# Adafruit_FTDI_Friend_Rev_A.net
KiCad netlist of a schematic drawn in EAGLE
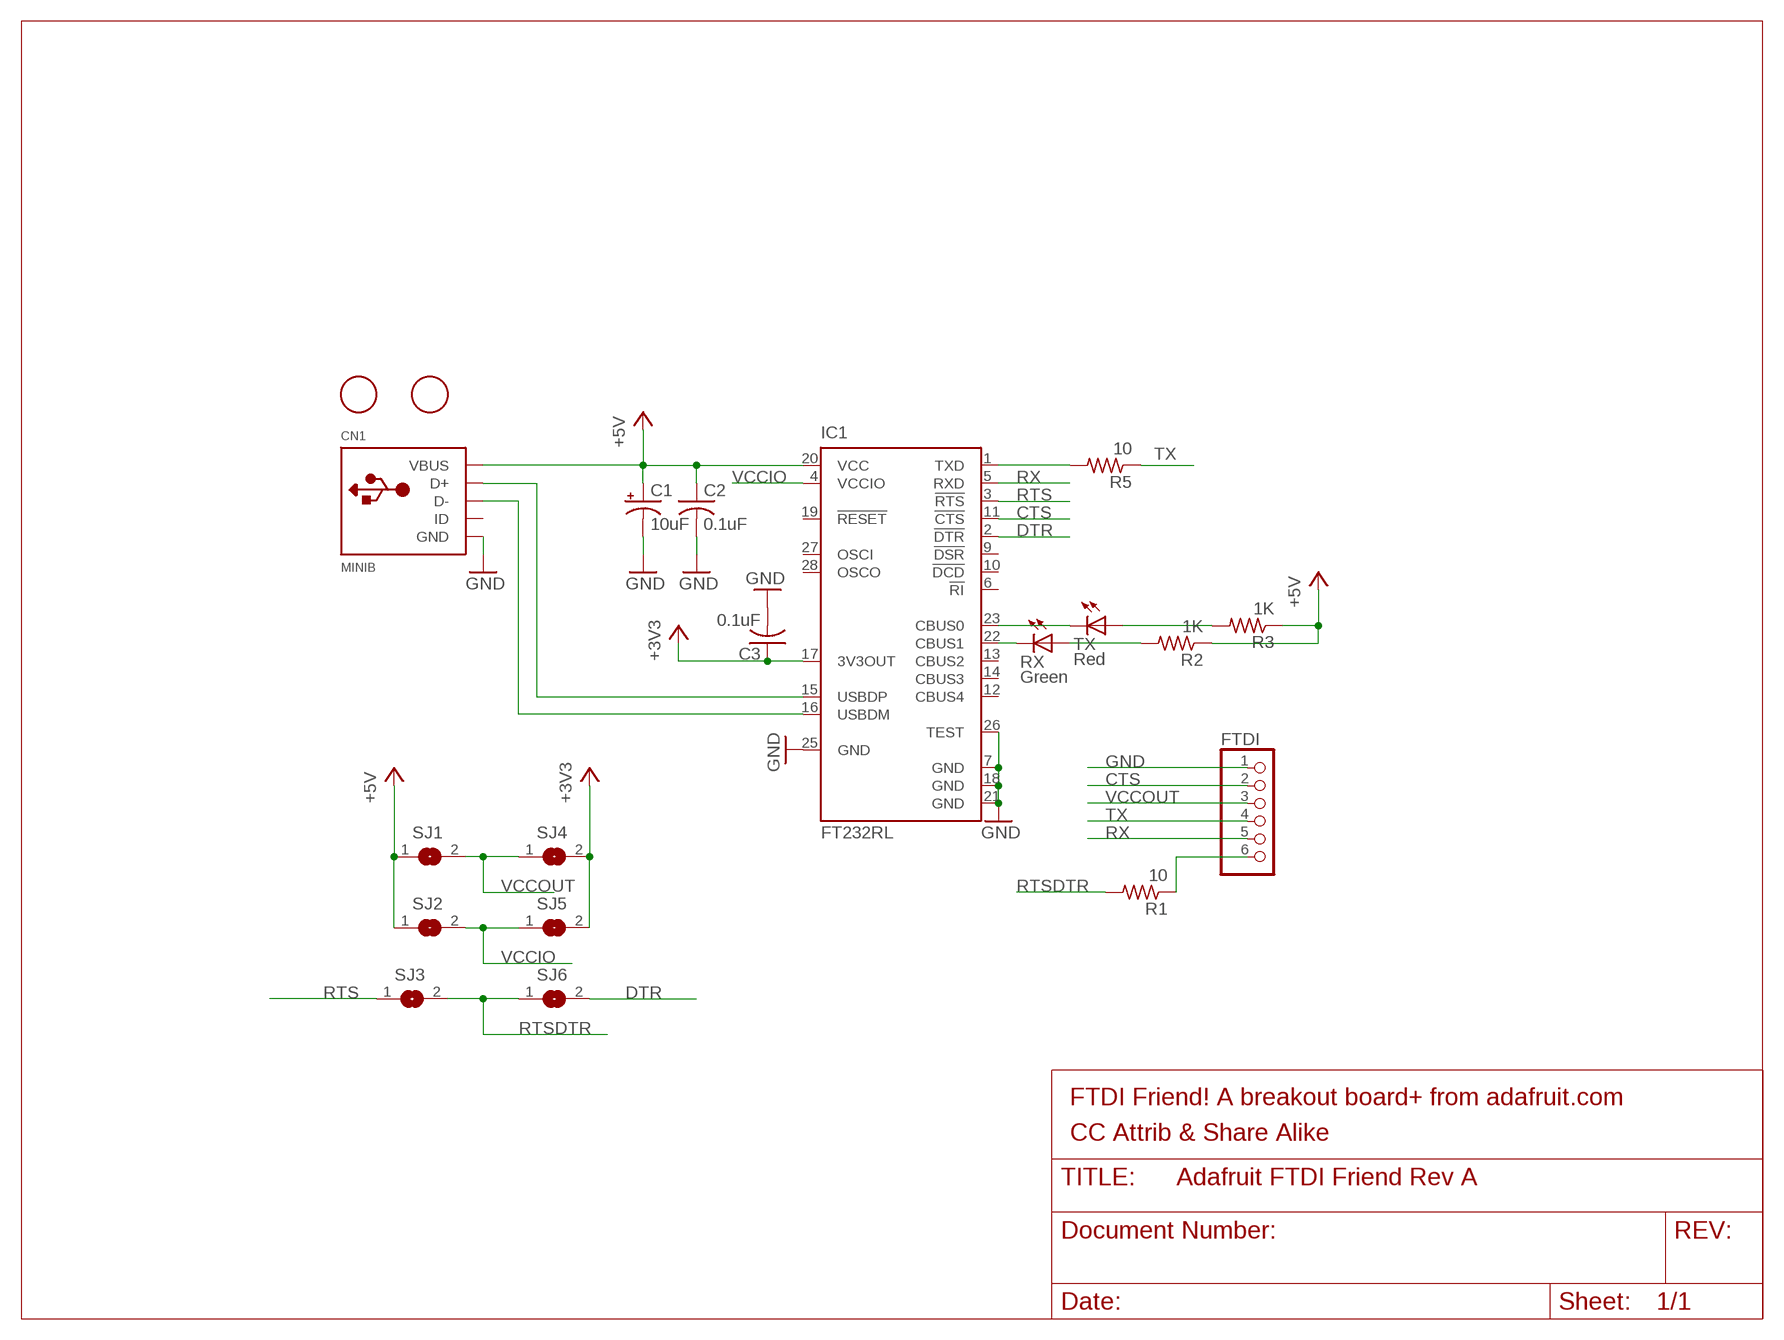
[diagram p0: schematic, sheet 1]

(export (version "E")
  (design (tool "Eeschema 10.0.6"))
  (components
    (comp (ref "C1")
      (value "10uF")
      (footprint "eagle-import:A_3216-18R")
      (libsource (lib "eagle-import") (part "CPOL-USA/3216-18R"))
    )
    (comp (ref "C2")
      (value "0.1uF")
      (footprint "eagle-import:C0805K")
      (libsource (lib "eagle-import") (part "C-USC0805K"))
    )
    (comp (ref "C3")
      (value "0.1uF")
      (footprint "eagle-import:C0805K")
      (libsource (lib "eagle-import") (part "C-USC0805K"))
    )
    (comp (ref "CN1")
      (value "MINIB")
      (footprint "eagle-import:USB-MINIB")
      (libsource (lib "eagle-import") (part "USBMINIB"))
    )
    (comp (ref "FTDI")
      (value "PINHD-1X6CB")
      (footprint "eagle-import:1X06-CLEANBIG")
      (libsource (lib "eagle-import") (part "PINHD-1X6CB"))
    )
    (comp (ref "IC1")
      (value "FT232RL")
      (footprint "eagle-import:SSOP28")
      (libsource (lib "eagle-import") (part "FT232RL"))
    )
    (comp (ref "R1")
      (value "10")
      (footprint "eagle-import:R0805")
      (libsource (lib "eagle-import") (part "R-US_R0805"))
    )
    (comp (ref "R2")
      (value "1K")
      (footprint "eagle-import:R0805")
      (libsource (lib "eagle-import") (part "R-US_R0805"))
    )
    (comp (ref "R3")
      (value "1K")
      (footprint "eagle-import:R0805")
      (libsource (lib "eagle-import") (part "R-US_R0805"))
    )
    (comp (ref "R5")
      (value "10")
      (footprint "eagle-import:R0805")
      (libsource (lib "eagle-import") (part "R-US_R0805"))
    )
    (comp (ref "RX")
      (value "Green")
      (footprint "eagle-import:CHIP-LED0805")
      (libsource (lib "eagle-import") (part "LEDCHIP-LED0805"))
    )
    (comp (ref "SJ1") (value "SJ") (footprint "eagle-import:SJ") (libsource (lib "eagle-import") (part "SJ")))
    (comp (ref "SJ2") (value "SJ") (footprint "eagle-import:SJ") (libsource (lib "eagle-import") (part "SJ")))
    (comp (ref "SJ3") (value "SJ") (footprint "eagle-import:SJ") (libsource (lib "eagle-import") (part "SJ")))
    (comp (ref "SJ4") (value "SJ") (footprint "eagle-import:SJ") (libsource (lib "eagle-import") (part "SJ")))
    (comp (ref "SJ5") (value "SJ") (footprint "eagle-import:SJ") (libsource (lib "eagle-import") (part "SJ")))
    (comp (ref "SJ6") (value "SJ") (footprint "eagle-import:SJ") (libsource (lib "eagle-import") (part "SJ")))
    (comp (ref "TX")
      (value "Red")
      (footprint "eagle-import:CHIP-LED0805")
      (libsource (lib "eagle-import") (part "LEDCHIP-LED0805"))
    )
    (comp (ref "U$1")
      (value "FIDUCIAL")
      (footprint "eagle-import:FIDUCIAL_1MM")
      (libsource (lib "eagle-import") (part "FIDUCIAL"))
    )
    (comp (ref "U$2")
      (value "FIDUCIAL")
      (footprint "eagle-import:FIDUCIAL_1MM")
      (libsource (lib "eagle-import") (part "FIDUCIAL"))
    )
  )
  (nets
    (net (code "1") (name "+3V3") (class "Default")
      (node (ref "C3") (pin "1") (pinfunction "1_1") (pintype "passive"))
      (node (ref "IC1") (pin "17") (pinfunction "3V3OUT_17") (pintype "input"))
      (node (ref "SJ4") (pin "2") (pinfunction "2_2") (pintype "passive"))
      (node (ref "SJ5") (pin "2") (pinfunction "2_2") (pintype "passive"))
    )
    (net (code "2") (name "+5V") (class "Default")
      (node (ref "C1") (pin "+") (pinfunction "+_+") (pintype "passive"))
      (node (ref "C2") (pin "1") (pinfunction "1_1") (pintype "passive"))
      (node (ref "CN1") (pin "VBUS") (pinfunction "VBUS_VBUS") (pintype "power_in"))
      (node (ref "IC1") (pin "20") (pinfunction "VCC_20") (pintype "input"))
      (node (ref "R2") (pin "1") (pinfunction "1_1") (pintype "passive"))
      (node (ref "R3") (pin "1") (pinfunction "1_1") (pintype "passive"))
      (node (ref "SJ1") (pin "1") (pinfunction "1_1") (pintype "passive"))
      (node (ref "SJ2") (pin "1") (pinfunction "1_1") (pintype "passive"))
    )
    (net (code "3") (name "/CTS") (class "Default")
      (node (ref "FTDI") (pin "2") (pinfunction "2_2") (pintype "passive"))
      (node (ref "IC1") (pin "11") (pinfunction "~{CTS}_11") (pintype "input"))
    )
    (net (code "4") (name "/DTR") (class "Default")
      (node (ref "IC1") (pin "2") (pinfunction "~{DTR}_2") (pintype "input"))
      (node (ref "SJ6") (pin "2") (pinfunction "2_2") (pintype "passive"))
    )
    (net (code "5") (name "/RTS") (class "Default")
      (node (ref "IC1") (pin "3") (pinfunction "~{RTS}_3") (pintype "input"))
      (node (ref "SJ3") (pin "1") (pinfunction "1_1") (pintype "passive"))
    )
    (net (code "6") (name "/RTSDTR") (class "Default")
      (node (ref "R1") (pin "2") (pinfunction "2_2") (pintype "passive"))
      (node (ref "SJ3") (pin "2") (pinfunction "2_2") (pintype "passive"))
      (node (ref "SJ6") (pin "1") (pinfunction "1_1") (pintype "passive"))
    )
    (net (code "7") (name "/RX") (class "Default")
      (node (ref "FTDI") (pin "5") (pinfunction "5_5") (pintype "passive"))
      (node (ref "IC1") (pin "5") (pinfunction "RXD_5") (pintype "input"))
    )
    (net (code "8") (name "/TX") (class "Default")
      (node (ref "FTDI") (pin "4") (pinfunction "4_4") (pintype "passive"))
      (node (ref "R5") (pin "1") (pinfunction "1_1") (pintype "passive"))
    )
    (net (code "9") (name "/VCCIO") (class "Default")
      (node (ref "IC1") (pin "4") (pinfunction "VCCIO_4") (pintype "input"))
      (node (ref "SJ2") (pin "2") (pinfunction "2_2") (pintype "passive"))
      (node (ref "SJ5") (pin "1") (pinfunction "1_1") (pintype "passive"))
    )
    (net (code "10") (name "/VCCOUT") (class "Default")
      (node (ref "FTDI") (pin "3") (pinfunction "3_3") (pintype "passive"))
      (node (ref "SJ1") (pin "2") (pinfunction "2_2") (pintype "passive"))
      (node (ref "SJ4") (pin "1") (pinfunction "1_1") (pintype "passive"))
    )
    (net (code "11") (name "GND") (class "Default")
      (node (ref "C1") (pin "-") (pinfunction "-_-") (pintype "passive"))
      (node (ref "C2") (pin "2") (pinfunction "2_2") (pintype "passive"))
      (node (ref "C3") (pin "2") (pinfunction "2_2") (pintype "passive"))
      (node (ref "CN1") (pin "GND") (pinfunction "GND_GND") (pintype "power_in"))
      (node (ref "FTDI") (pin "1") (pinfunction "1_1") (pintype "passive"))
      (node (ref "IC1") (pin "18") (pinfunction "GND_18") (pintype "input"))
      (node (ref "IC1") (pin "21") (pinfunction "GND_21") (pintype "input"))
      (node (ref "IC1") (pin "25") (pinfunction "GND_25") (pintype "input"))
      (node (ref "IC1") (pin "26") (pinfunction "TEST_26") (pintype "input"))
      (node (ref "IC1") (pin "7") (pinfunction "GND_7") (pintype "input"))
    )
    (net (code "12") (name "Net-(FTDI-Pad6)") (class "Default")
      (node (ref "FTDI") (pin "6") (pinfunction "6_6") (pintype "passive"))
      (node (ref "R1") (pin "1") (pinfunction "1_1") (pintype "passive"))
    )
    (net (code "13") (name "Net-(IC1-CBUS0)") (class "Default")
      (node (ref "IC1") (pin "23") (pinfunction "CBUS0_23") (pintype "input"))
      (node (ref "TX") (pin "C") (pinfunction "C_C") (pintype "passive"))
    )
    (net (code "14") (name "Net-(IC1-CBUS1)") (class "Default")
      (node (ref "IC1") (pin "22") (pinfunction "CBUS1_22") (pintype "input"))
      (node (ref "RX") (pin "C") (pinfunction "C_C") (pintype "passive"))
    )
    (net (code "15") (name "Net-(IC1-TXD)") (class "Default")
      (node (ref "IC1") (pin "1") (pinfunction "TXD_1") (pintype "input"))
      (node (ref "R5") (pin "2") (pinfunction "2_2") (pintype "passive"))
    )
    (net (code "16") (name "Net-(IC1-USBDM)") (class "Default")
      (node (ref "CN1") (pin "D-") (pinfunction "D-_D-") (pintype "bidirectional"))
      (node (ref "IC1") (pin "16") (pinfunction "USBDM_16") (pintype "input"))
    )
    (net (code "17") (name "Net-(IC1-USBDP)") (class "Default")
      (node (ref "CN1") (pin "D+") (pinfunction "D+_D+") (pintype "bidirectional"))
      (node (ref "IC1") (pin "15") (pinfunction "USBDP_15") (pintype "input"))
    )
    (net (code "18") (name "Net-(R2-Pad2)") (class "Default")
      (node (ref "R2") (pin "2") (pinfunction "2_2") (pintype "passive"))
      (node (ref "RX") (pin "A") (pinfunction "A_A") (pintype "passive"))
    )
    (net (code "19") (name "Net-(R3-Pad2)") (class "Default")
      (node (ref "R3") (pin "2") (pinfunction "2_2") (pintype "passive"))
      (node (ref "TX") (pin "A") (pinfunction "A_A") (pintype "passive"))
    )
    (net (code "20") (name "unconnected-(CN1-PadID)") (class "Default")
      (node (ref "CN1") (pin "ID") (pinfunction "ID_ID") (pintype "bidirectional"))
    )
    (net (code "21") (name "unconnected-(IC1-CBUS2-Pad13)") (class "Default")
      (node (ref "IC1") (pin "13") (pinfunction "CBUS2_13") (pintype "input"))
    )
    (net (code "22") (name "unconnected-(IC1-CBUS3-Pad14)") (class "Default")
      (node (ref "IC1") (pin "14") (pinfunction "CBUS3_14") (pintype "input"))
    )
    (net (code "23") (name "unconnected-(IC1-CBUS4-Pad12)") (class "Default")
      (node (ref "IC1") (pin "12") (pinfunction "CBUS4_12") (pintype "input"))
    )
    (net (code "24") (name "unconnected-(IC1-OSCI-Pad27)") (class "Default")
      (node (ref "IC1") (pin "27") (pinfunction "OSCI_27") (pintype "input"))
    )
    (net (code "25") (name "unconnected-(IC1-OSCO-Pad28)") (class "Default")
      (node (ref "IC1") (pin "28") (pinfunction "OSCO_28") (pintype "input"))
    )
    (net (code "26") (name "unconnected-(IC1-~{DCD}-Pad10)") (class "Default")
      (node (ref "IC1") (pin "10") (pinfunction "~{DCD}_10") (pintype "input"))
    )
    (net (code "27") (name "unconnected-(IC1-~{DSR}-Pad9)") (class "Default")
      (node (ref "IC1") (pin "9") (pinfunction "~{DSR}_9") (pintype "input"))
    )
    (net (code "28") (name "unconnected-(IC1-~{RESET}-Pad19)") (class "Default")
      (node (ref "IC1") (pin "19") (pinfunction "~{RESET}_19") (pintype "input"))
    )
    (net (code "29") (name "unconnected-(IC1-~{RI}-Pad6)") (class "Default")
      (node (ref "IC1") (pin "6") (pinfunction "~{RI}_6") (pintype "input"))
    )
  )
)
